# OBC_SRAM.net
KiCad netlist of a schematic drawn in Altium Designer
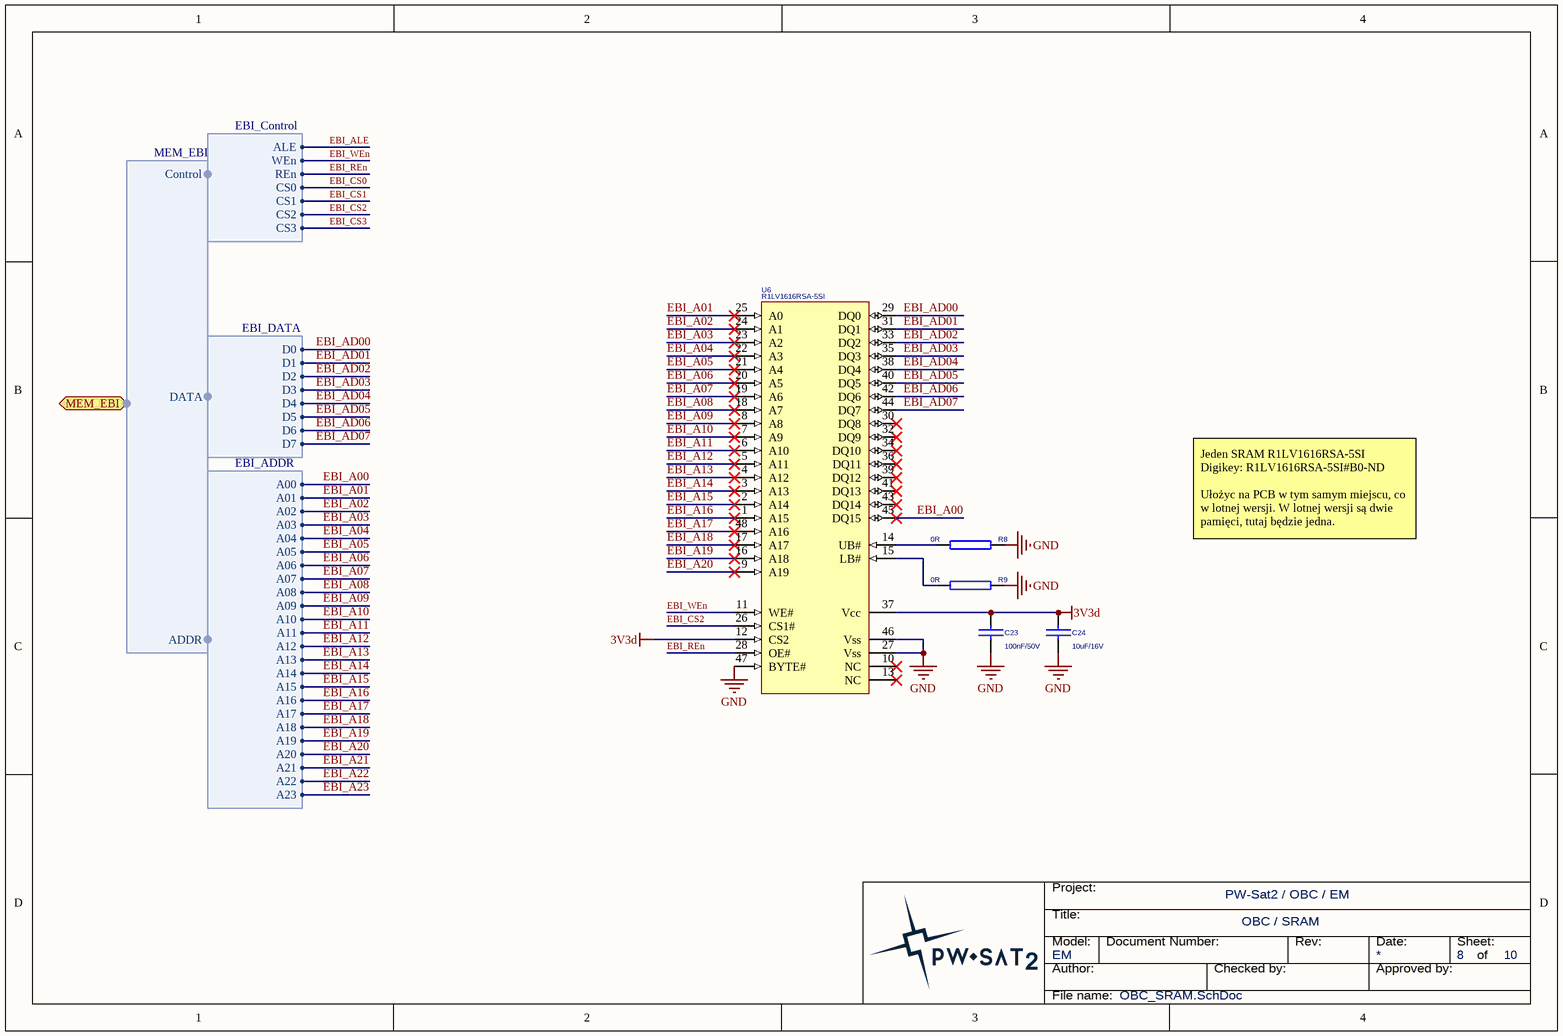
[diagram p0: OBC_SRAM.SchDoc]

(export (version "E")
  (design (tool "Eeschema 10.0.6"))
  (components
    (comp (ref "C23")
      (value "100nF/50V")
      (footprint "C0603")
      (description "Capacitator")
      (fields (field (name "VOLTAGE") "50V"))
      (libsource (lib "SchLib") (part "CAP"))
    )
    (comp (ref "C24")
      (value "10uF/16V")
      (footprint "C1206")
      (description "Capacitator")
      (fields (field (name "VOLTAGE") "16V"))
      (libsource (lib "SchLib") (part "CAP"))
    )
    (comp (ref "R8")
      (value "0R")
      (footprint "R0603")
      (description "Resistor")
      (libsource (lib "SchLib") (part "RES"))
    )
    (comp (ref "R9")
      (value "0R")
      (footprint "R0603")
      (description "Resistor")
      (libsource (lib "SchLib") (part "RES"))
    )
    (comp (ref "U6")
      (value "R1LV1616RSA-5SI")
      (footprint "TSSOP50P2000X125-48N")
      (description "IC SRAM 16MBIT 55NS 48TSOP")
      (fields (field (name "MANUFACTURER") "Renesas Electronics"))
      (libsource (lib "OBC") (part "R1LV1616RSA-5SI"))
    )
  )
  (nets
    (net (code "2") (name "/EBI_A00") (class "Default")
      (node (ref "U6") (pin "45") (pinfunction "DQ15_45") (pintype "bidirectional+no_connect"))
    )
    (net (code "3") (name "/EBI_A01") (class "Default")
      (node (ref "U6") (pin "25") (pinfunction "A0_25") (pintype "input+no_connect"))
    )
    (net (code "4") (name "/EBI_A02") (class "Default")
      (node (ref "U6") (pin "24") (pinfunction "A1_24") (pintype "input+no_connect"))
    )
    (net (code "5") (name "/EBI_A03") (class "Default")
      (node (ref "U6") (pin "23") (pinfunction "A2_23") (pintype "input+no_connect"))
    )
    (net (code "6") (name "/EBI_A04") (class "Default")
      (node (ref "U6") (pin "22") (pinfunction "A3_22") (pintype "input+no_connect"))
    )
    (net (code "7") (name "/EBI_A05") (class "Default")
      (node (ref "U6") (pin "21") (pinfunction "A4_21") (pintype "input+no_connect"))
    )
    (net (code "8") (name "/EBI_A06") (class "Default")
      (node (ref "U6") (pin "20") (pinfunction "A5_20") (pintype "input+no_connect"))
    )
    (net (code "9") (name "/EBI_A07") (class "Default")
      (node (ref "U6") (pin "19") (pinfunction "A6_19") (pintype "input+no_connect"))
    )
    (net (code "10") (name "/EBI_A08") (class "Default")
      (node (ref "U6") (pin "18") (pinfunction "A7_18") (pintype "input+no_connect"))
    )
    (net (code "11") (name "/EBI_A09") (class "Default")
      (node (ref "U6") (pin "8") (pinfunction "A8_8") (pintype "input+no_connect"))
    )
    (net (code "12") (name "/EBI_A10") (class "Default")
      (node (ref "U6") (pin "7") (pinfunction "A9_7") (pintype "input+no_connect"))
    )
    (net (code "13") (name "/EBI_A11") (class "Default")
      (node (ref "U6") (pin "6") (pinfunction "A10_6") (pintype "input+no_connect"))
    )
    (net (code "14") (name "/EBI_A12") (class "Default")
      (node (ref "U6") (pin "5") (pinfunction "A11_5") (pintype "input+no_connect"))
    )
    (net (code "15") (name "/EBI_A13") (class "Default")
      (node (ref "U6") (pin "4") (pinfunction "A12_4") (pintype "input+no_connect"))
    )
    (net (code "16") (name "/EBI_A14") (class "Default")
      (node (ref "U6") (pin "3") (pinfunction "A13_3") (pintype "input+no_connect"))
    )
    (net (code "17") (name "/EBI_A15") (class "Default")
      (node (ref "U6") (pin "2") (pinfunction "A14_2") (pintype "input+no_connect"))
    )
    (net (code "18") (name "/EBI_A16") (class "Default")
      (node (ref "U6") (pin "1") (pinfunction "A15_1") (pintype "input+no_connect"))
    )
    (net (code "19") (name "/EBI_A17") (class "Default")
      (node (ref "U6") (pin "48") (pinfunction "A16_48") (pintype "input+no_connect"))
    )
    (net (code "20") (name "/EBI_A18") (class "Default")
      (node (ref "U6") (pin "17") (pinfunction "A17_17") (pintype "input+no_connect"))
    )
    (net (code "21") (name "/EBI_A19") (class "Default")
      (node (ref "U6") (pin "16") (pinfunction "A18_16") (pintype "input+no_connect"))
    )
    (net (code "22") (name "/EBI_A20") (class "Default")
      (node (ref "U6") (pin "9") (pinfunction "A19_9") (pintype "input+no_connect"))
    )
    (net (code "26") (name "/EBI_AD00") (class "Default")
      (node (ref "U6") (pin "29") (pinfunction "DQ0_29") (pintype "bidirectional"))
    )
    (net (code "27") (name "/EBI_AD01") (class "Default")
      (node (ref "U6") (pin "31") (pinfunction "DQ1_31") (pintype "bidirectional"))
    )
    (net (code "28") (name "/EBI_AD02") (class "Default")
      (node (ref "U6") (pin "33") (pinfunction "DQ2_33") (pintype "bidirectional"))
    )
    (net (code "29") (name "/EBI_AD03") (class "Default")
      (node (ref "U6") (pin "35") (pinfunction "DQ3_35") (pintype "bidirectional"))
    )
    (net (code "30") (name "/EBI_AD04") (class "Default")
      (node (ref "U6") (pin "38") (pinfunction "DQ4_38") (pintype "bidirectional"))
    )
    (net (code "31") (name "/EBI_AD05") (class "Default")
      (node (ref "U6") (pin "40") (pinfunction "DQ5_40") (pintype "bidirectional"))
    )
    (net (code "32") (name "/EBI_AD06") (class "Default")
      (node (ref "U6") (pin "42") (pinfunction "DQ6_42") (pintype "bidirectional"))
    )
    (net (code "33") (name "/EBI_AD07") (class "Default")
      (node (ref "U6") (pin "44") (pinfunction "DQ7_44") (pintype "bidirectional"))
    )
    (net (code "37") (name "/EBI_CS2") (class "Default")
      (node (ref "U6") (pin "26") (pinfunction "CS1#_26") (pintype "input"))
    )
    (net (code "39") (name "/EBI_REn") (class "Default")
      (node (ref "U6") (pin "28") (pinfunction "OE#_28") (pintype "input"))
    )
    (net (code "40") (name "/EBI_WEn") (class "Default")
      (node (ref "U6") (pin "11") (pinfunction "WE#_11") (pintype "input"))
    )
    (net (code "42") (name "3V3d") (class "Default")
      (node (ref "C23") (pin "1") (pintype "passive"))
      (node (ref "C24") (pin "1") (pintype "passive"))
      (node (ref "U6") (pin "12") (pinfunction "CS2_12") (pintype "input"))
      (node (ref "U6") (pin "37") (pinfunction "Vcc_37") (pintype "passive"))
    )
    (net (code "43") (name "GND") (class "Default")
      (node (ref "C23") (pin "2") (pintype "passive"))
      (node (ref "C24") (pin "2") (pintype "passive"))
      (node (ref "R8") (pin "2") (pintype "passive"))
      (node (ref "R9") (pin "2") (pintype "passive"))
      (node (ref "U6") (pin "27") (pinfunction "Vss_27") (pintype "passive"))
      (node (ref "U6") (pin "46") (pinfunction "Vss_46") (pintype "passive"))
      (node (ref "U6") (pin "47") (pinfunction "BYTE#_47") (pintype "input"))
    )
    (net (code "44") (name "Net-(U6-LB#)") (class "Default")
      (node (ref "R9") (pin "1") (pintype "passive"))
      (node (ref "U6") (pin "15") (pinfunction "LB#_15") (pintype "input"))
    )
    (net (code "45") (name "Net-(U6-UB#)") (class "Default")
      (node (ref "R8") (pin "1") (pintype "passive"))
      (node (ref "U6") (pin "14") (pinfunction "UB#_14") (pintype "input"))
    )
    (net (code "46") (name "unconnected-(U6-DQ8-Pad30)") (class "Default")
      (node (ref "U6") (pin "30") (pinfunction "DQ8_30") (pintype "bidirectional+no_connect"))
    )
    (net (code "47") (name "unconnected-(U6-DQ9-Pad32)") (class "Default")
      (node (ref "U6") (pin "32") (pinfunction "DQ9_32") (pintype "bidirectional+no_connect"))
    )
    (net (code "48") (name "unconnected-(U6-DQ10-Pad34)") (class "Default")
      (node (ref "U6") (pin "34") (pinfunction "DQ10_34") (pintype "bidirectional+no_connect"))
    )
    (net (code "49") (name "unconnected-(U6-DQ11-Pad36)") (class "Default")
      (node (ref "U6") (pin "36") (pinfunction "DQ11_36") (pintype "bidirectional+no_connect"))
    )
    (net (code "50") (name "unconnected-(U6-DQ12-Pad39)") (class "Default")
      (node (ref "U6") (pin "39") (pinfunction "DQ12_39") (pintype "bidirectional+no_connect"))
    )
    (net (code "51") (name "unconnected-(U6-DQ13-Pad41)") (class "Default")
      (node (ref "U6") (pin "41") (pinfunction "DQ13_41") (pintype "bidirectional+no_connect"))
    )
    (net (code "52") (name "unconnected-(U6-DQ14-Pad43)") (class "Default")
      (node (ref "U6") (pin "43") (pinfunction "DQ14_43") (pintype "bidirectional+no_connect"))
    )
    (net (code "53") (name "unconnected-(U6-NC-Pad10)") (class "Default")
      (node (ref "U6") (pin "10") (pinfunction "NC_10") (pintype "passive+no_connect"))
    )
    (net (code "54") (name "unconnected-(U6-NC-Pad13)") (class "Default")
      (node (ref "U6") (pin "13") (pinfunction "NC_13") (pintype "passive+no_connect"))
    )
  )
)
